# 4_Power_switching.net
KiCad netlist of a schematic drawn in Altium Designer
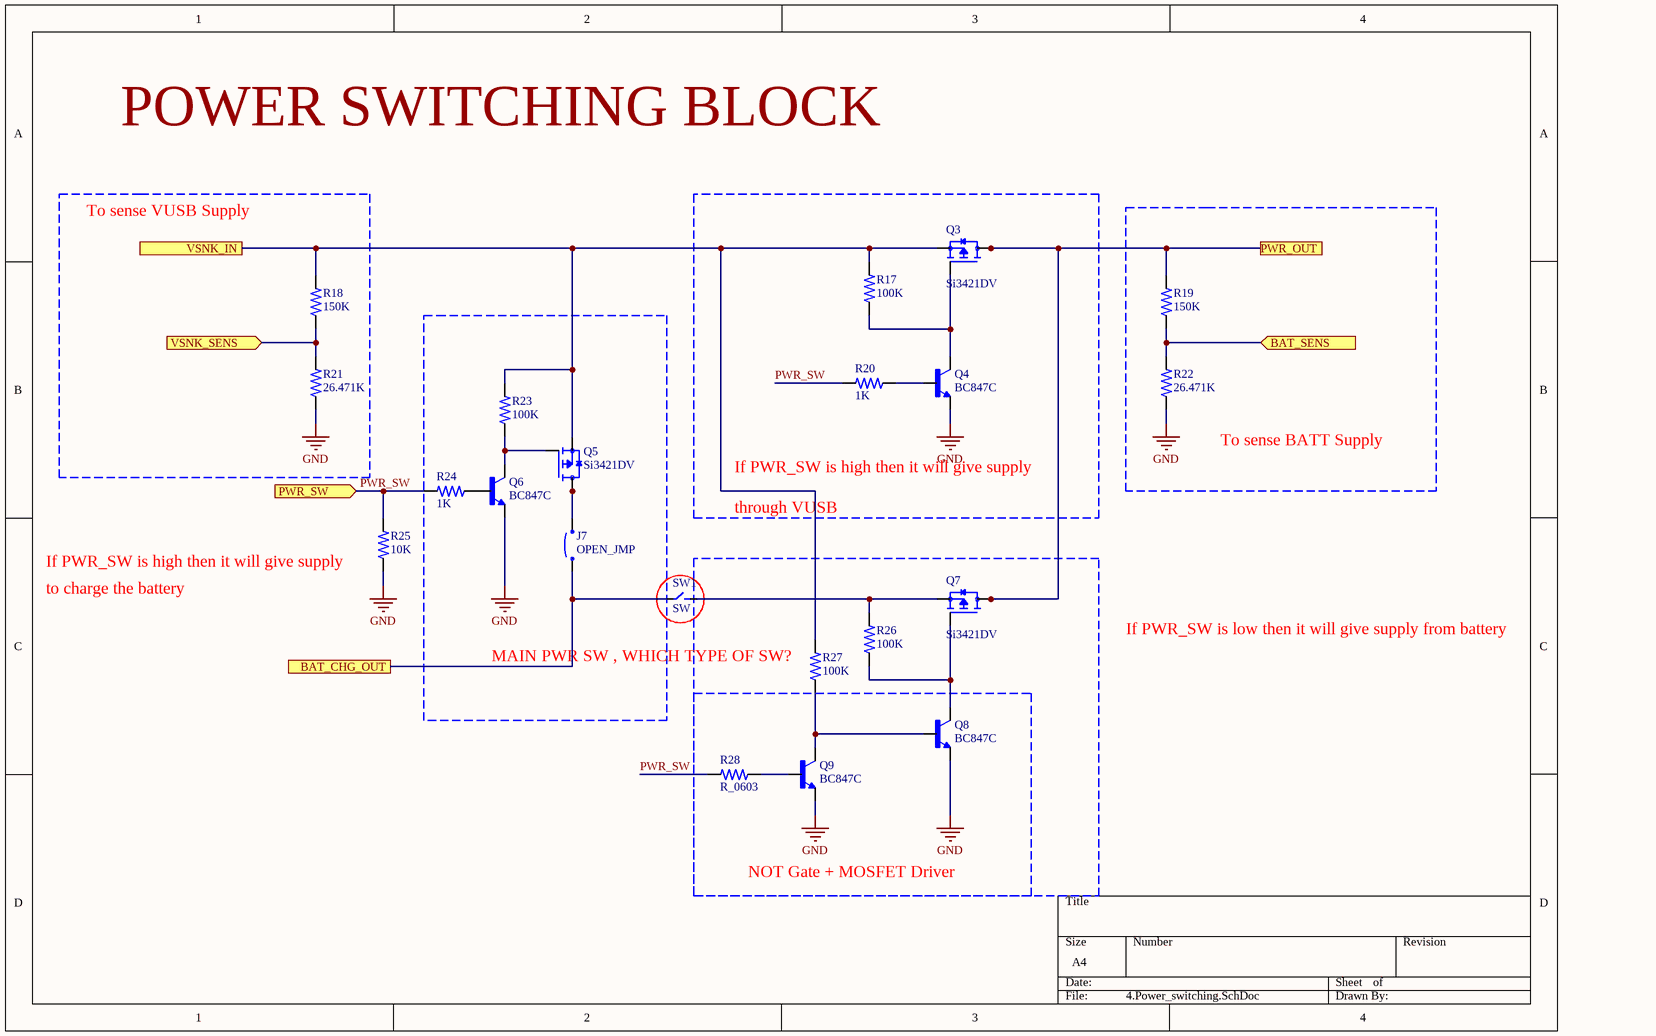
[diagram p0: 4.Power_switching.SchDoc]

(export (version "E")
  (design (tool "Eeschema 10.0.6"))
  (components
    (comp (ref "J7")
      (value "OPEN_JMP")
      (footprint "PcbLib:OPEN_JMP")
      (libsource (lib "Schlib") (part "OPEN_JMP"))
    )
    (comp (ref "Q3")
      (value "Si3421DV")
      (footprint "TSOP-6")
      (fields (field (name "MFR") "Vishay Siliconix"))
      (libsource (lib "Schlib") (part "Si3421DV"))
    )
    (comp (ref "Q4")
      (value "BC847C")
      (footprint "SOT-23-3")
      (fields (field (name "MFR") "Nexperia"))
      (libsource (lib "Schlib") (part "BC847C"))
    )
    (comp (ref "Q5")
      (value "Si3421DV")
      (footprint "TSOP-6")
      (fields (field (name "MFR") "Vishay Siliconix"))
      (libsource (lib "Schlib") (part "Si3421DV"))
    )
    (comp (ref "Q6")
      (value "BC847C")
      (footprint "SOT-23-3")
      (fields (field (name "MFR") "Nexperia"))
      (libsource (lib "Schlib") (part "BC847C"))
    )
    (comp (ref "Q7")
      (value "Si3421DV")
      (footprint "TSOP-6")
      (fields (field (name "MFR") "Vishay Siliconix"))
      (libsource (lib "Schlib") (part "Si3421DV"))
    )
    (comp (ref "Q8")
      (value "BC847C")
      (footprint "SOT-23-3")
      (fields (field (name "MFR") "Nexperia"))
      (libsource (lib "Schlib") (part "BC847C"))
    )
    (comp (ref "Q9")
      (value "BC847C")
      (footprint "SOT-23-3")
      (fields (field (name "MFR") "Nexperia"))
      (libsource (lib "Schlib") (part "BC847C"))
    )
    (comp (ref "R17") (value "100K") (footprint "R_0603") (libsource (lib "Schlib") (part "R_0603")))
    (comp (ref "R18") (value "150K") (footprint "R_0603") (libsource (lib "Schlib") (part "R_0603")))
    (comp (ref "R19") (value "150K") (footprint "R_0603") (libsource (lib "Schlib") (part "R_0603")))
    (comp (ref "R20") (value "1K") (footprint "R_0603") (libsource (lib "Schlib") (part "R_0603")))
    (comp (ref "R21") (value "26.471K") (footprint "R_0603") (libsource (lib "Schlib") (part "R_0603")))
    (comp (ref "R22") (value "26.471K") (footprint "R_0603") (libsource (lib "Schlib") (part "R_0603")))
    (comp (ref "R23") (value "100K") (footprint "R_0603") (libsource (lib "Schlib") (part "R_0603")))
    (comp (ref "R24") (value "1K") (footprint "R_0603") (libsource (lib "Schlib") (part "R_0603")))
    (comp (ref "R25") (value "10K") (footprint "R_0603") (libsource (lib "Schlib") (part "R_0603")))
    (comp (ref "R26") (value "100K") (footprint "R_0603") (libsource (lib "Schlib") (part "R_0603")))
    (comp (ref "R27") (value "100K") (footprint "R_0603") (libsource (lib "Schlib") (part "R_0603")))
    (comp (ref "R28") (value "R_0603") (footprint "R_0603") (libsource (lib "Schlib") (part "R_0603")))
    (comp (ref "SW1") (value "SW") (libsource (lib "Schlib") (part "SW")))
  )
  (nets
    (net (code "1") (name "/BAT_CHG_OUT") (class "Default")
      (node (ref "J7") (pin "1") (pinfunction "1_1") (pintype "passive"))
      (node (ref "SW1") (pin "1") (pinfunction "1_1") (pintype "passive"))
    )
    (net (code "2") (name "/BAT_SENS") (class "Default")
      (node (ref "R19") (pin "1") (pinfunction "1_1") (pintype "passive"))
      (node (ref "R22") (pin "2") (pinfunction "2_2") (pintype "passive"))
    )
    (net (code "3") (name "/PWR_OUT") (class "Default")
      (node (ref "Q3") (pin "1") (pinfunction "D_1") (pintype "passive"))
      (node (ref "Q3") (pin "2") (pinfunction "D_2") (pintype "passive"))
      (node (ref "Q3") (pin "5") (pinfunction "D_5") (pintype "passive"))
      (node (ref "Q3") (pin "6") (pinfunction "D_6") (pintype "passive"))
      (node (ref "Q7") (pin "1") (pinfunction "D_1") (pintype "passive"))
      (node (ref "Q7") (pin "2") (pinfunction "D_2") (pintype "passive"))
      (node (ref "Q7") (pin "5") (pinfunction "D_5") (pintype "passive"))
      (node (ref "Q7") (pin "6") (pinfunction "D_6") (pintype "passive"))
      (node (ref "R19") (pin "2") (pinfunction "2_2") (pintype "passive"))
    )
    (net (code "4") (name "/PWR_SW") (class "Default")
      (node (ref "R20") (pin "2") (pinfunction "2_2") (pintype "passive"))
      (node (ref "R24") (pin "2") (pinfunction "2_2") (pintype "passive"))
      (node (ref "R25") (pin "2") (pinfunction "2_2") (pintype "passive"))
      (node (ref "R28") (pin "2") (pinfunction "2_2") (pintype "passive"))
    )
    (net (code "5") (name "/VSNK_IN") (class "Default")
      (node (ref "Q3") (pin "4") (pinfunction "S_4") (pintype "passive"))
      (node (ref "Q5") (pin "4") (pinfunction "S_4") (pintype "passive"))
      (node (ref "R17") (pin "2") (pinfunction "2_2") (pintype "passive"))
      (node (ref "R18") (pin "2") (pinfunction "2_2") (pintype "passive"))
      (node (ref "R23") (pin "2") (pinfunction "2_2") (pintype "passive"))
      (node (ref "R27") (pin "2") (pinfunction "2_2") (pintype "passive"))
    )
    (net (code "6") (name "/VSNK_SENS") (class "Default")
      (node (ref "R18") (pin "1") (pinfunction "1_1") (pintype "passive"))
      (node (ref "R21") (pin "2") (pinfunction "2_2") (pintype "passive"))
    )
    (net (code "7") (name "GND") (class "Default")
      (node (ref "Q4") (pin "2") (pinfunction "E_2") (pintype "passive"))
      (node (ref "Q6") (pin "2") (pinfunction "E_2") (pintype "passive"))
      (node (ref "Q8") (pin "2") (pinfunction "E_2") (pintype "passive"))
      (node (ref "Q9") (pin "2") (pinfunction "E_2") (pintype "passive"))
      (node (ref "R21") (pin "1") (pinfunction "1_1") (pintype "passive"))
      (node (ref "R22") (pin "1") (pinfunction "1_1") (pintype "passive"))
      (node (ref "R25") (pin "1") (pinfunction "1_1") (pintype "passive"))
    )
    (net (code "8") (name "Net-(J7-Pad2)") (class "Default")
      (node (ref "J7") (pin "2") (pinfunction "2_2") (pintype "passive"))
      (node (ref "Q5") (pin "1") (pinfunction "D_1") (pintype "passive"))
      (node (ref "Q5") (pin "2") (pinfunction "D_2") (pintype "passive"))
      (node (ref "Q5") (pin "5") (pinfunction "D_5") (pintype "passive"))
      (node (ref "Q5") (pin "6") (pinfunction "D_6") (pintype "passive"))
    )
    (net (code "9") (name "Net-(Q3-G)") (class "Default")
      (node (ref "Q3") (pin "3") (pinfunction "G_3") (pintype "passive"))
      (node (ref "Q4") (pin "3") (pinfunction "C_3") (pintype "passive"))
      (node (ref "R17") (pin "1") (pinfunction "1_1") (pintype "passive"))
    )
    (net (code "10") (name "Net-(Q4-B)") (class "Default")
      (node (ref "Q4") (pin "1") (pinfunction "B_1") (pintype "passive"))
      (node (ref "R20") (pin "1") (pinfunction "1_1") (pintype "passive"))
    )
    (net (code "11") (name "Net-(Q5-G)") (class "Default")
      (node (ref "Q5") (pin "3") (pinfunction "G_3") (pintype "passive"))
      (node (ref "Q6") (pin "3") (pinfunction "C_3") (pintype "passive"))
      (node (ref "R23") (pin "1") (pinfunction "1_1") (pintype "passive"))
    )
    (net (code "12") (name "Net-(Q6-B)") (class "Default")
      (node (ref "Q6") (pin "1") (pinfunction "B_1") (pintype "passive"))
      (node (ref "R24") (pin "1") (pinfunction "1_1") (pintype "passive"))
    )
    (net (code "13") (name "Net-(Q7-G)") (class "Default")
      (node (ref "Q7") (pin "3") (pinfunction "G_3") (pintype "passive"))
      (node (ref "Q8") (pin "3") (pinfunction "C_3") (pintype "passive"))
      (node (ref "R26") (pin "1") (pinfunction "1_1") (pintype "passive"))
    )
    (net (code "14") (name "Net-(Q7-S)") (class "Default")
      (node (ref "Q7") (pin "4") (pinfunction "S_4") (pintype "passive"))
      (node (ref "R26") (pin "2") (pinfunction "2_2") (pintype "passive"))
      (node (ref "SW1") (pin "2") (pinfunction "2_2") (pintype "passive"))
    )
    (net (code "15") (name "Net-(Q8-B)") (class "Default")
      (node (ref "Q8") (pin "1") (pinfunction "B_1") (pintype "passive"))
      (node (ref "Q9") (pin "3") (pinfunction "C_3") (pintype "passive"))
      (node (ref "R27") (pin "1") (pinfunction "1_1") (pintype "passive"))
    )
    (net (code "16") (name "Net-(Q9-B)") (class "Default")
      (node (ref "Q9") (pin "1") (pinfunction "B_1") (pintype "passive"))
      (node (ref "R28") (pin "1") (pinfunction "1_1") (pintype "passive"))
    )
  )
)
